# RPI_M_LED.net
KiCad netlist of a schematic drawn in EAGLE
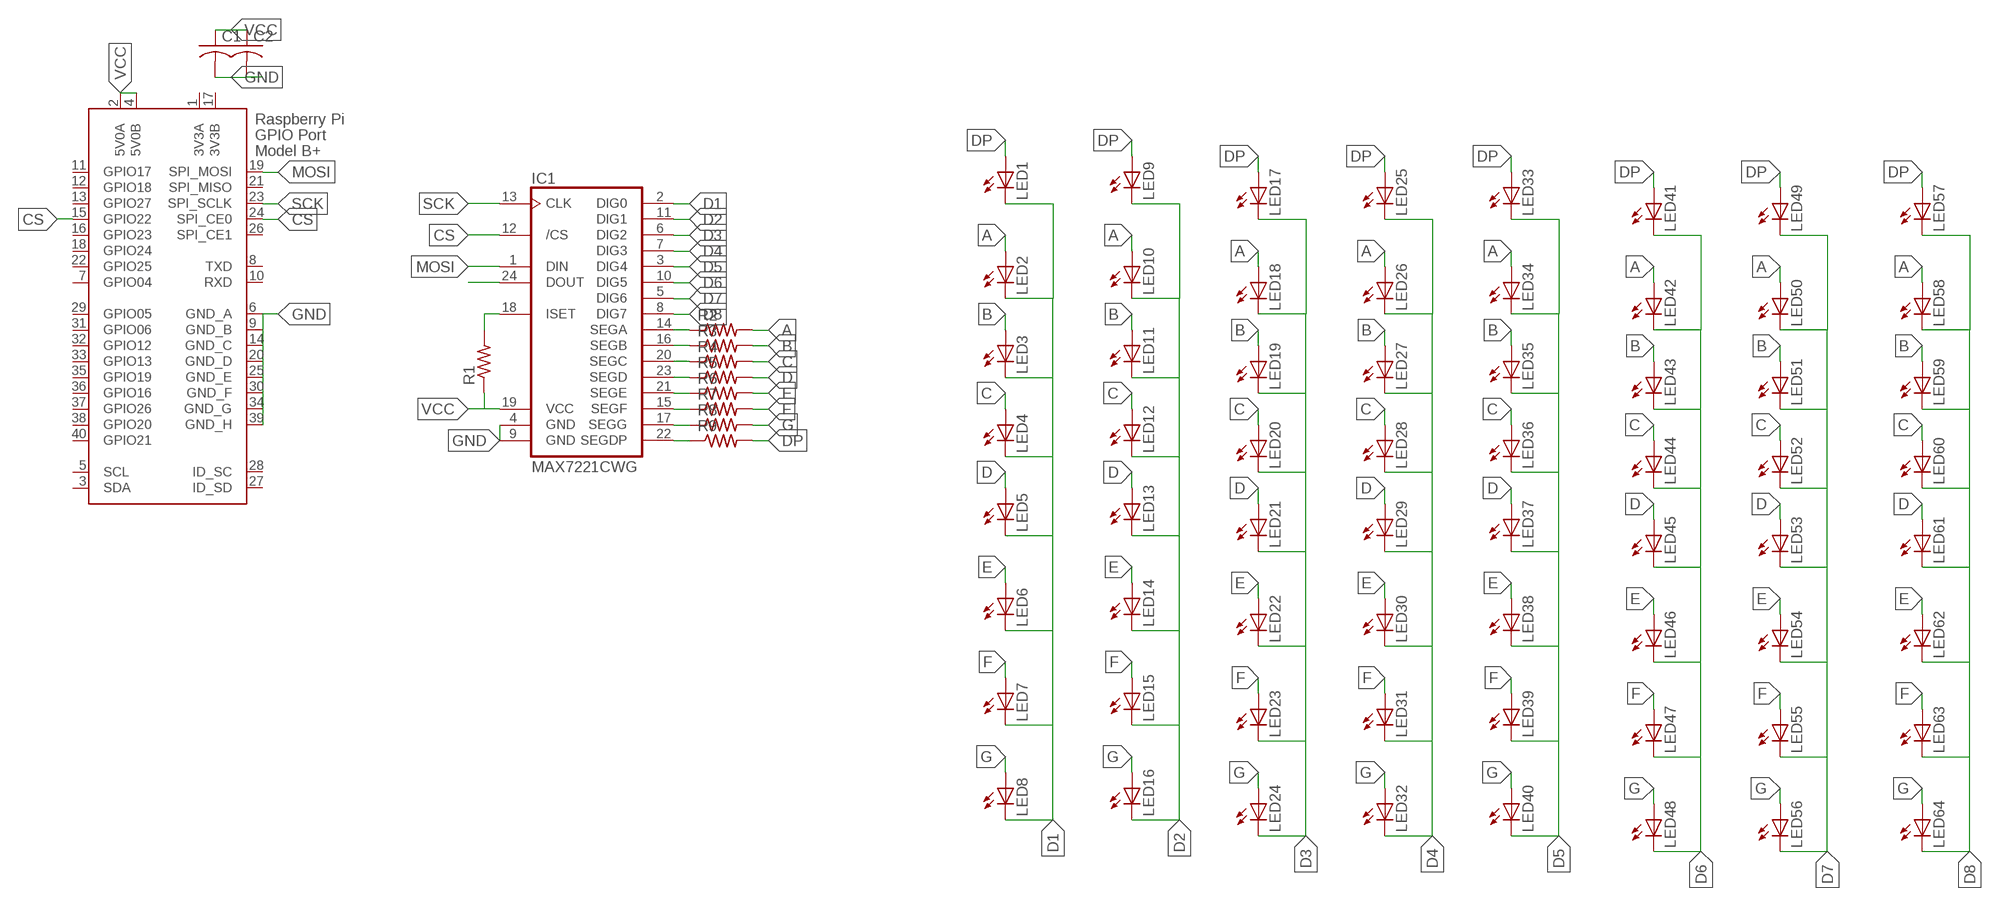
[diagram p0: schematic, sheet 1]

(export (version "E")
  (design (tool "Eeschema 10.0.6"))
  (components
    (comp (ref "C1")
      (value "C-USC0805")
      (footprint "eagle-import:C0805")
      (libsource (lib "eagle-import") (part "C-USC0805"))
    )
    (comp (ref "C2")
      (value "C-USC0805")
      (footprint "eagle-import:C0805")
      (libsource (lib "eagle-import") (part "C-USC0805"))
    )
    (comp (ref "IC1")
      (value "MAX7221CWG")
      (footprint "eagle-import:SO24W")
      (libsource (lib "eagle-import") (part "MAX7221WGC"))
    )
    (comp (ref "LED1")
      (value "LEDCHIPLED_0603")
      (footprint "eagle-import:CHIPLED_0603")
      (libsource (lib "eagle-import") (part "LEDCHIPLED_0603"))
    )
    (comp (ref "LED2")
      (value "LEDCHIPLED_0603")
      (footprint "eagle-import:CHIPLED_0603")
      (libsource (lib "eagle-import") (part "LEDCHIPLED_0603"))
    )
    (comp (ref "LED3")
      (value "LEDCHIPLED_0603")
      (footprint "eagle-import:CHIPLED_0603")
      (libsource (lib "eagle-import") (part "LEDCHIPLED_0603"))
    )
    (comp (ref "LED4")
      (value "LEDCHIPLED_0603")
      (footprint "eagle-import:CHIPLED_0603")
      (libsource (lib "eagle-import") (part "LEDCHIPLED_0603"))
    )
    (comp (ref "LED5")
      (value "LEDCHIPLED_0603")
      (footprint "eagle-import:CHIPLED_0603")
      (libsource (lib "eagle-import") (part "LEDCHIPLED_0603"))
    )
    (comp (ref "LED6")
      (value "LEDCHIPLED_0603")
      (footprint "eagle-import:CHIPLED_0603")
      (libsource (lib "eagle-import") (part "LEDCHIPLED_0603"))
    )
    (comp (ref "LED7")
      (value "LEDCHIPLED_0603")
      (footprint "eagle-import:CHIPLED_0603")
      (libsource (lib "eagle-import") (part "LEDCHIPLED_0603"))
    )
    (comp (ref "LED8")
      (value "LEDCHIPLED_0603")
      (footprint "eagle-import:CHIPLED_0603")
      (libsource (lib "eagle-import") (part "LEDCHIPLED_0603"))
    )
    (comp (ref "LED9")
      (value "LEDCHIPLED_0603")
      (footprint "eagle-import:CHIPLED_0603")
      (libsource (lib "eagle-import") (part "LEDCHIPLED_0603"))
    )
    (comp (ref "LED10")
      (value "LEDCHIPLED_0603")
      (footprint "eagle-import:CHIPLED_0603")
      (libsource (lib "eagle-import") (part "LEDCHIPLED_0603"))
    )
    (comp (ref "LED11")
      (value "LEDCHIPLED_0603")
      (footprint "eagle-import:CHIPLED_0603")
      (libsource (lib "eagle-import") (part "LEDCHIPLED_0603"))
    )
    (comp (ref "LED12")
      (value "LEDCHIPLED_0603")
      (footprint "eagle-import:CHIPLED_0603")
      (libsource (lib "eagle-import") (part "LEDCHIPLED_0603"))
    )
    (comp (ref "LED13")
      (value "LEDCHIPLED_0603")
      (footprint "eagle-import:CHIPLED_0603")
      (libsource (lib "eagle-import") (part "LEDCHIPLED_0603"))
    )
    (comp (ref "LED14")
      (value "LEDCHIPLED_0603")
      (footprint "eagle-import:CHIPLED_0603")
      (libsource (lib "eagle-import") (part "LEDCHIPLED_0603"))
    )
    (comp (ref "LED15")
      (value "LEDCHIPLED_0603")
      (footprint "eagle-import:CHIPLED_0603")
      (libsource (lib "eagle-import") (part "LEDCHIPLED_0603"))
    )
    (comp (ref "LED16")
      (value "LEDCHIPLED_0603")
      (footprint "eagle-import:CHIPLED_0603")
      (libsource (lib "eagle-import") (part "LEDCHIPLED_0603"))
    )
    (comp (ref "LED17")
      (value "LEDCHIPLED_0603")
      (footprint "eagle-import:CHIPLED_0603")
      (libsource (lib "eagle-import") (part "LEDCHIPLED_0603"))
    )
    (comp (ref "LED18")
      (value "LEDCHIPLED_0603")
      (footprint "eagle-import:CHIPLED_0603")
      (libsource (lib "eagle-import") (part "LEDCHIPLED_0603"))
    )
    (comp (ref "LED19")
      (value "LEDCHIPLED_0603")
      (footprint "eagle-import:CHIPLED_0603")
      (libsource (lib "eagle-import") (part "LEDCHIPLED_0603"))
    )
    (comp (ref "LED20")
      (value "LEDCHIPLED_0603")
      (footprint "eagle-import:CHIPLED_0603")
      (libsource (lib "eagle-import") (part "LEDCHIPLED_0603"))
    )
    (comp (ref "LED21")
      (value "LEDCHIPLED_0603")
      (footprint "eagle-import:CHIPLED_0603")
      (libsource (lib "eagle-import") (part "LEDCHIPLED_0603"))
    )
    (comp (ref "LED22")
      (value "LEDCHIPLED_0603")
      (footprint "eagle-import:CHIPLED_0603")
      (libsource (lib "eagle-import") (part "LEDCHIPLED_0603"))
    )
    (comp (ref "LED23")
      (value "LEDCHIPLED_0603")
      (footprint "eagle-import:CHIPLED_0603")
      (libsource (lib "eagle-import") (part "LEDCHIPLED_0603"))
    )
    (comp (ref "LED24")
      (value "LEDCHIPLED_0603")
      (footprint "eagle-import:CHIPLED_0603")
      (libsource (lib "eagle-import") (part "LEDCHIPLED_0603"))
    )
    (comp (ref "LED25")
      (value "LEDCHIPLED_0603")
      (footprint "eagle-import:CHIPLED_0603")
      (libsource (lib "eagle-import") (part "LEDCHIPLED_0603"))
    )
    (comp (ref "LED26")
      (value "LEDCHIPLED_0603")
      (footprint "eagle-import:CHIPLED_0603")
      (libsource (lib "eagle-import") (part "LEDCHIPLED_0603"))
    )
    (comp (ref "LED27")
      (value "LEDCHIPLED_0603")
      (footprint "eagle-import:CHIPLED_0603")
      (libsource (lib "eagle-import") (part "LEDCHIPLED_0603"))
    )
    (comp (ref "LED28")
      (value "LEDCHIPLED_0603")
      (footprint "eagle-import:CHIPLED_0603")
      (libsource (lib "eagle-import") (part "LEDCHIPLED_0603"))
    )
    (comp (ref "LED29")
      (value "LEDCHIPLED_0603")
      (footprint "eagle-import:CHIPLED_0603")
      (libsource (lib "eagle-import") (part "LEDCHIPLED_0603"))
    )
    (comp (ref "LED30")
      (value "LEDCHIPLED_0603")
      (footprint "eagle-import:CHIPLED_0603")
      (libsource (lib "eagle-import") (part "LEDCHIPLED_0603"))
    )
    (comp (ref "LED31")
      (value "LEDCHIPLED_0603")
      (footprint "eagle-import:CHIPLED_0603")
      (libsource (lib "eagle-import") (part "LEDCHIPLED_0603"))
    )
    (comp (ref "LED32")
      (value "LEDCHIPLED_0603")
      (footprint "eagle-import:CHIPLED_0603")
      (libsource (lib "eagle-import") (part "LEDCHIPLED_0603"))
    )
    (comp (ref "LED33")
      (value "LEDCHIPLED_0603")
      (footprint "eagle-import:CHIPLED_0603")
      (libsource (lib "eagle-import") (part "LEDCHIPLED_0603"))
    )
    (comp (ref "LED34")
      (value "LEDCHIPLED_0603")
      (footprint "eagle-import:CHIPLED_0603")
      (libsource (lib "eagle-import") (part "LEDCHIPLED_0603"))
    )
    (comp (ref "LED35")
      (value "LEDCHIPLED_0603")
      (footprint "eagle-import:CHIPLED_0603")
      (libsource (lib "eagle-import") (part "LEDCHIPLED_0603"))
    )
    (comp (ref "LED36")
      (value "LEDCHIPLED_0603")
      (footprint "eagle-import:CHIPLED_0603")
      (libsource (lib "eagle-import") (part "LEDCHIPLED_0603"))
    )
    (comp (ref "LED37")
      (value "LEDCHIPLED_0603")
      (footprint "eagle-import:CHIPLED_0603")
      (libsource (lib "eagle-import") (part "LEDCHIPLED_0603"))
    )
    (comp (ref "LED38")
      (value "LEDCHIPLED_0603")
      (footprint "eagle-import:CHIPLED_0603")
      (libsource (lib "eagle-import") (part "LEDCHIPLED_0603"))
    )
    (comp (ref "LED39")
      (value "LEDCHIPLED_0603")
      (footprint "eagle-import:CHIPLED_0603")
      (libsource (lib "eagle-import") (part "LEDCHIPLED_0603"))
    )
    (comp (ref "LED40")
      (value "LEDCHIPLED_0603")
      (footprint "eagle-import:CHIPLED_0603")
      (libsource (lib "eagle-import") (part "LEDCHIPLED_0603"))
    )
    (comp (ref "LED41")
      (value "LEDCHIPLED_0603")
      (footprint "eagle-import:CHIPLED_0603")
      (libsource (lib "eagle-import") (part "LEDCHIPLED_0603"))
    )
    (comp (ref "LED42")
      (value "LEDCHIPLED_0603")
      (footprint "eagle-import:CHIPLED_0603")
      (libsource (lib "eagle-import") (part "LEDCHIPLED_0603"))
    )
    (comp (ref "LED43")
      (value "LEDCHIPLED_0603")
      (footprint "eagle-import:CHIPLED_0603")
      (libsource (lib "eagle-import") (part "LEDCHIPLED_0603"))
    )
    (comp (ref "LED44")
      (value "LEDCHIPLED_0603")
      (footprint "eagle-import:CHIPLED_0603")
      (libsource (lib "eagle-import") (part "LEDCHIPLED_0603"))
    )
    (comp (ref "LED45")
      (value "LEDCHIPLED_0603")
      (footprint "eagle-import:CHIPLED_0603")
      (libsource (lib "eagle-import") (part "LEDCHIPLED_0603"))
    )
    (comp (ref "LED46")
      (value "LEDCHIPLED_0603")
      (footprint "eagle-import:CHIPLED_0603")
      (libsource (lib "eagle-import") (part "LEDCHIPLED_0603"))
    )
    (comp (ref "LED47")
      (value "LEDCHIPLED_0603")
      (footprint "eagle-import:CHIPLED_0603")
      (libsource (lib "eagle-import") (part "LEDCHIPLED_0603"))
    )
    (comp (ref "LED48")
      (value "LEDCHIPLED_0603")
      (footprint "eagle-import:CHIPLED_0603")
      (libsource (lib "eagle-import") (part "LEDCHIPLED_0603"))
    )
    (comp (ref "LED49")
      (value "LEDCHIPLED_0603")
      (footprint "eagle-import:CHIPLED_0603")
      (libsource (lib "eagle-import") (part "LEDCHIPLED_0603"))
    )
    (comp (ref "LED50")
      (value "LEDCHIPLED_0603")
      (footprint "eagle-import:CHIPLED_0603")
      (libsource (lib "eagle-import") (part "LEDCHIPLED_0603"))
    )
    (comp (ref "LED51")
      (value "LEDCHIPLED_0603")
      (footprint "eagle-import:CHIPLED_0603")
      (libsource (lib "eagle-import") (part "LEDCHIPLED_0603"))
    )
    (comp (ref "LED52")
      (value "LEDCHIPLED_0603")
      (footprint "eagle-import:CHIPLED_0603")
      (libsource (lib "eagle-import") (part "LEDCHIPLED_0603"))
    )
    (comp (ref "LED53")
      (value "LEDCHIPLED_0603")
      (footprint "eagle-import:CHIPLED_0603")
      (libsource (lib "eagle-import") (part "LEDCHIPLED_0603"))
    )
    (comp (ref "LED54")
      (value "LEDCHIPLED_0603")
      (footprint "eagle-import:CHIPLED_0603")
      (libsource (lib "eagle-import") (part "LEDCHIPLED_0603"))
    )
    (comp (ref "LED55")
      (value "LEDCHIPLED_0603")
      (footprint "eagle-import:CHIPLED_0603")
      (libsource (lib "eagle-import") (part "LEDCHIPLED_0603"))
    )
    (comp (ref "LED56")
      (value "LEDCHIPLED_0603")
      (footprint "eagle-import:CHIPLED_0603")
      (libsource (lib "eagle-import") (part "LEDCHIPLED_0603"))
    )
    (comp (ref "LED57")
      (value "LEDCHIPLED_0603")
      (footprint "eagle-import:CHIPLED_0603")
      (libsource (lib "eagle-import") (part "LEDCHIPLED_0603"))
    )
    (comp (ref "LED58")
      (value "LEDCHIPLED_0603")
      (footprint "eagle-import:CHIPLED_0603")
      (libsource (lib "eagle-import") (part "LEDCHIPLED_0603"))
    )
    (comp (ref "LED59")
      (value "LEDCHIPLED_0603")
      (footprint "eagle-import:CHIPLED_0603")
      (libsource (lib "eagle-import") (part "LEDCHIPLED_0603"))
    )
    (comp (ref "LED60")
      (value "LEDCHIPLED_0603")
      (footprint "eagle-import:CHIPLED_0603")
      (libsource (lib "eagle-import") (part "LEDCHIPLED_0603"))
    )
    (comp (ref "LED61")
      (value "LEDCHIPLED_0603")
      (footprint "eagle-import:CHIPLED_0603")
      (libsource (lib "eagle-import") (part "LEDCHIPLED_0603"))
    )
    (comp (ref "LED62")
      (value "LEDCHIPLED_0603")
      (footprint "eagle-import:CHIPLED_0603")
      (libsource (lib "eagle-import") (part "LEDCHIPLED_0603"))
    )
    (comp (ref "LED63")
      (value "LEDCHIPLED_0603")
      (footprint "eagle-import:CHIPLED_0603")
      (libsource (lib "eagle-import") (part "LEDCHIPLED_0603"))
    )
    (comp (ref "LED64")
      (value "LEDCHIPLED_0603")
      (footprint "eagle-import:CHIPLED_0603")
      (libsource (lib "eagle-import") (part "LEDCHIPLED_0603"))
    )
    (comp (ref "R1")
      (value "R-US_R0805")
      (footprint "eagle-import:R0805")
      (libsource (lib "eagle-import") (part "R-US_R0805"))
    )
    (comp (ref "R2")
      (value "R-US_R0603")
      (footprint "eagle-import:R0603")
      (libsource (lib "eagle-import") (part "R-US_R0603"))
    )
    (comp (ref "R3")
      (value "R-US_R0603")
      (footprint "eagle-import:R0603")
      (libsource (lib "eagle-import") (part "R-US_R0603"))
    )
    (comp (ref "R4")
      (value "R-US_R0603")
      (footprint "eagle-import:R0603")
      (libsource (lib "eagle-import") (part "R-US_R0603"))
    )
    (comp (ref "R5")
      (value "R-US_R0603")
      (footprint "eagle-import:R0603")
      (libsource (lib "eagle-import") (part "R-US_R0603"))
    )
    (comp (ref "R6")
      (value "R-US_R0603")
      (footprint "eagle-import:R0603")
      (libsource (lib "eagle-import") (part "R-US_R0603"))
    )
    (comp (ref "R7")
      (value "R-US_R0603")
      (footprint "eagle-import:R0603")
      (libsource (lib "eagle-import") (part "R-US_R0603"))
    )
    (comp (ref "R8")
      (value "R-US_R0603")
      (footprint "eagle-import:R0603")
      (libsource (lib "eagle-import") (part "R-US_R0603"))
    )
    (comp (ref "R9")
      (value "R-US_R0603")
      (footprint "eagle-import:R0603")
      (libsource (lib "eagle-import") (part "R-US_R0603"))
    )
    (comp (ref "X1")
      (value "RASPI_GPIO_B+#_PIN")
      (footprint "eagle-import:RASPI_GPIO_B+_PIN")
      (libsource (lib "eagle-import") (part "RASPI_GPIO_B+#_PIN"))
    )
  )
  (nets
    (net (code "1") (name "/3V3A") (class "Default")
      (node (ref "X1") (pin "1") (pinfunction "3V3A_1") (pintype "power_in"))
    )
    (net (code "2") (name "/3V3B") (class "Default")
      (node (ref "X1") (pin "17") (pinfunction "3V3B_17") (pintype "power_in"))
    )
    (net (code "3") (name "A") (class "Default")
      (node (ref "LED10") (pin "A") (pinfunction "A_A") (pintype "passive"))
      (node (ref "LED18") (pin "A") (pinfunction "A_A") (pintype "passive"))
      (node (ref "LED2") (pin "A") (pinfunction "A_A") (pintype "passive"))
      (node (ref "LED26") (pin "A") (pinfunction "A_A") (pintype "passive"))
      (node (ref "LED34") (pin "A") (pinfunction "A_A") (pintype "passive"))
      (node (ref "LED42") (pin "A") (pinfunction "A_A") (pintype "passive"))
      (node (ref "LED50") (pin "A") (pinfunction "A_A") (pintype "passive"))
      (node (ref "LED58") (pin "A") (pinfunction "A_A") (pintype "passive"))
      (node (ref "R2") (pin "2") (pinfunction "2_2") (pintype "passive"))
    )
    (net (code "4") (name "B") (class "Default")
      (node (ref "LED11") (pin "A") (pinfunction "A_A") (pintype "passive"))
      (node (ref "LED19") (pin "A") (pinfunction "A_A") (pintype "passive"))
      (node (ref "LED27") (pin "A") (pinfunction "A_A") (pintype "passive"))
      (node (ref "LED3") (pin "A") (pinfunction "A_A") (pintype "passive"))
      (node (ref "LED35") (pin "A") (pinfunction "A_A") (pintype "passive"))
      (node (ref "LED43") (pin "A") (pinfunction "A_A") (pintype "passive"))
      (node (ref "LED51") (pin "A") (pinfunction "A_A") (pintype "passive"))
      (node (ref "LED59") (pin "A") (pinfunction "A_A") (pintype "passive"))
      (node (ref "R3") (pin "2") (pinfunction "2_2") (pintype "passive"))
    )
    (net (code "5") (name "C") (class "Default")
      (node (ref "LED12") (pin "A") (pinfunction "A_A") (pintype "passive"))
      (node (ref "LED20") (pin "A") (pinfunction "A_A") (pintype "passive"))
      (node (ref "LED28") (pin "A") (pinfunction "A_A") (pintype "passive"))
      (node (ref "LED36") (pin "A") (pinfunction "A_A") (pintype "passive"))
      (node (ref "LED4") (pin "A") (pinfunction "A_A") (pintype "passive"))
      (node (ref "LED44") (pin "A") (pinfunction "A_A") (pintype "passive"))
      (node (ref "LED52") (pin "A") (pinfunction "A_A") (pintype "passive"))
      (node (ref "LED60") (pin "A") (pinfunction "A_A") (pintype "passive"))
      (node (ref "R4") (pin "2") (pinfunction "2_2") (pintype "passive"))
    )
    (net (code "6") (name "CS") (class "Default")
      (node (ref "IC1") (pin "12") (pinfunction "/CS_12") (pintype "input"))
      (node (ref "X1") (pin "15") (pinfunction "GPIO22_15") (pintype "bidirectional"))
      (node (ref "X1") (pin "24") (pinfunction "SPI_CE0_24") (pintype "bidirectional"))
    )
    (net (code "7") (name "D") (class "Default")
      (node (ref "LED13") (pin "A") (pinfunction "A_A") (pintype "passive"))
      (node (ref "LED21") (pin "A") (pinfunction "A_A") (pintype "passive"))
      (node (ref "LED29") (pin "A") (pinfunction "A_A") (pintype "passive"))
      (node (ref "LED37") (pin "A") (pinfunction "A_A") (pintype "passive"))
      (node (ref "LED45") (pin "A") (pinfunction "A_A") (pintype "passive"))
      (node (ref "LED5") (pin "A") (pinfunction "A_A") (pintype "passive"))
      (node (ref "LED53") (pin "A") (pinfunction "A_A") (pintype "passive"))
      (node (ref "LED61") (pin "A") (pinfunction "A_A") (pintype "passive"))
      (node (ref "R5") (pin "2") (pinfunction "2_2") (pintype "passive"))
    )
    (net (code "8") (name "D1") (class "Default")
      (node (ref "IC1") (pin "2") (pinfunction "DIG0_2") (pintype "open_collector"))
      (node (ref "LED1") (pin "C") (pinfunction "C_C") (pintype "passive"))
      (node (ref "LED2") (pin "C") (pinfunction "C_C") (pintype "passive"))
      (node (ref "LED3") (pin "C") (pinfunction "C_C") (pintype "passive"))
      (node (ref "LED4") (pin "C") (pinfunction "C_C") (pintype "passive"))
      (node (ref "LED5") (pin "C") (pinfunction "C_C") (pintype "passive"))
      (node (ref "LED6") (pin "C") (pinfunction "C_C") (pintype "passive"))
      (node (ref "LED7") (pin "C") (pinfunction "C_C") (pintype "passive"))
      (node (ref "LED8") (pin "C") (pinfunction "C_C") (pintype "passive"))
    )
    (net (code "9") (name "D2") (class "Default")
      (node (ref "IC1") (pin "11") (pinfunction "DIG1_11") (pintype "open_collector"))
      (node (ref "LED10") (pin "C") (pinfunction "C_C") (pintype "passive"))
      (node (ref "LED11") (pin "C") (pinfunction "C_C") (pintype "passive"))
      (node (ref "LED12") (pin "C") (pinfunction "C_C") (pintype "passive"))
      (node (ref "LED13") (pin "C") (pinfunction "C_C") (pintype "passive"))
      (node (ref "LED14") (pin "C") (pinfunction "C_C") (pintype "passive"))
      (node (ref "LED15") (pin "C") (pinfunction "C_C") (pintype "passive"))
      (node (ref "LED16") (pin "C") (pinfunction "C_C") (pintype "passive"))
      (node (ref "LED9") (pin "C") (pinfunction "C_C") (pintype "passive"))
    )
    (net (code "10") (name "D3") (class "Default")
      (node (ref "IC1") (pin "6") (pinfunction "DIG2_6") (pintype "open_collector"))
      (node (ref "LED17") (pin "C") (pinfunction "C_C") (pintype "passive"))
      (node (ref "LED18") (pin "C") (pinfunction "C_C") (pintype "passive"))
      (node (ref "LED19") (pin "C") (pinfunction "C_C") (pintype "passive"))
      (node (ref "LED20") (pin "C") (pinfunction "C_C") (pintype "passive"))
      (node (ref "LED21") (pin "C") (pinfunction "C_C") (pintype "passive"))
      (node (ref "LED22") (pin "C") (pinfunction "C_C") (pintype "passive"))
      (node (ref "LED23") (pin "C") (pinfunction "C_C") (pintype "passive"))
      (node (ref "LED24") (pin "C") (pinfunction "C_C") (pintype "passive"))
    )
    (net (code "11") (name "D4") (class "Default")
      (node (ref "IC1") (pin "7") (pinfunction "DIG3_7") (pintype "open_collector"))
      (node (ref "LED25") (pin "C") (pinfunction "C_C") (pintype "passive"))
      (node (ref "LED26") (pin "C") (pinfunction "C_C") (pintype "passive"))
      (node (ref "LED27") (pin "C") (pinfunction "C_C") (pintype "passive"))
      (node (ref "LED28") (pin "C") (pinfunction "C_C") (pintype "passive"))
      (node (ref "LED29") (pin "C") (pinfunction "C_C") (pintype "passive"))
      (node (ref "LED30") (pin "C") (pinfunction "C_C") (pintype "passive"))
      (node (ref "LED31") (pin "C") (pinfunction "C_C") (pintype "passive"))
      (node (ref "LED32") (pin "C") (pinfunction "C_C") (pintype "passive"))
    )
    (net (code "12") (name "D5") (class "Default")
      (node (ref "IC1") (pin "3") (pinfunction "DIG4_3") (pintype "open_collector"))
      (node (ref "LED33") (pin "C") (pinfunction "C_C") (pintype "passive"))
      (node (ref "LED34") (pin "C") (pinfunction "C_C") (pintype "passive"))
      (node (ref "LED35") (pin "C") (pinfunction "C_C") (pintype "passive"))
      (node (ref "LED36") (pin "C") (pinfunction "C_C") (pintype "passive"))
      (node (ref "LED37") (pin "C") (pinfunction "C_C") (pintype "passive"))
      (node (ref "LED38") (pin "C") (pinfunction "C_C") (pintype "passive"))
      (node (ref "LED39") (pin "C") (pinfunction "C_C") (pintype "passive"))
      (node (ref "LED40") (pin "C") (pinfunction "C_C") (pintype "passive"))
    )
    (net (code "13") (name "D6") (class "Default")
      (node (ref "IC1") (pin "10") (pinfunction "DIG5_10") (pintype "open_collector"))
      (node (ref "LED41") (pin "C") (pinfunction "C_C") (pintype "passive"))
      (node (ref "LED42") (pin "C") (pinfunction "C_C") (pintype "passive"))
      (node (ref "LED43") (pin "C") (pinfunction "C_C") (pintype "passive"))
      (node (ref "LED44") (pin "C") (pinfunction "C_C") (pintype "passive"))
      (node (ref "LED45") (pin "C") (pinfunction "C_C") (pintype "passive"))
      (node (ref "LED46") (pin "C") (pinfunction "C_C") (pintype "passive"))
      (node (ref "LED47") (pin "C") (pinfunction "C_C") (pintype "passive"))
      (node (ref "LED48") (pin "C") (pinfunction "C_C") (pintype "passive"))
    )
    (net (code "14") (name "D7") (class "Default")
      (node (ref "IC1") (pin "5") (pinfunction "DIG6_5") (pintype "open_collector"))
      (node (ref "LED49") (pin "C") (pinfunction "C_C") (pintype "passive"))
      (node (ref "LED50") (pin "C") (pinfunction "C_C") (pintype "passive"))
      (node (ref "LED51") (pin "C") (pinfunction "C_C") (pintype "passive"))
      (node (ref "LED52") (pin "C") (pinfunction "C_C") (pintype "passive"))
      (node (ref "LED53") (pin "C") (pinfunction "C_C") (pintype "passive"))
      (node (ref "LED54") (pin "C") (pinfunction "C_C") (pintype "passive"))
      (node (ref "LED55") (pin "C") (pinfunction "C_C") (pintype "passive"))
      (node (ref "LED56") (pin "C") (pinfunction "C_C") (pintype "passive"))
    )
    (net (code "15") (name "D8") (class "Default")
      (node (ref "IC1") (pin "8") (pinfunction "DIG7_8") (pintype "open_collector"))
      (node (ref "LED57") (pin "C") (pinfunction "C_C") (pintype "passive"))
      (node (ref "LED58") (pin "C") (pinfunction "C_C") (pintype "passive"))
      (node (ref "LED59") (pin "C") (pinfunction "C_C") (pintype "passive"))
      (node (ref "LED60") (pin "C") (pinfunction "C_C") (pintype "passive"))
      (node (ref "LED61") (pin "C") (pinfunction "C_C") (pintype "passive"))
      (node (ref "LED62") (pin "C") (pinfunction "C_C") (pintype "passive"))
      (node (ref "LED63") (pin "C") (pinfunction "C_C") (pintype "passive"))
      (node (ref "LED64") (pin "C") (pinfunction "C_C") (pintype "passive"))
    )
    (net (code "16") (name "DP") (class "Default")
      (node (ref "LED1") (pin "A") (pinfunction "A_A") (pintype "passive"))
      (node (ref "LED17") (pin "A") (pinfunction "A_A") (pintype "passive"))
      (node (ref "LED25") (pin "A") (pinfunction "A_A") (pintype "passive"))
      (node (ref "LED33") (pin "A") (pinfunction "A_A") (pintype "passive"))
      (node (ref "LED41") (pin "A") (pinfunction "A_A") (pintype "passive"))
      (node (ref "LED49") (pin "A") (pinfunction "A_A") (pintype "passive"))
      (node (ref "LED57") (pin "A") (pinfunction "A_A") (pintype "passive"))
      (node (ref "LED9") (pin "A") (pinfunction "A_A") (pintype "passive"))
      (node (ref "R9") (pin "2") (pinfunction "2_2") (pintype "passive"))
    )
    (net (code "17") (name "E") (class "Default")
      (node (ref "LED14") (pin "A") (pinfunction "A_A") (pintype "passive"))
      (node (ref "LED22") (pin "A") (pinfunction "A_A") (pintype "passive"))
      (node (ref "LED30") (pin "A") (pinfunction "A_A") (pintype "passive"))
      (node (ref "LED38") (pin "A") (pinfunction "A_A") (pintype "passive"))
      (node (ref "LED46") (pin "A") (pinfunction "A_A") (pintype "passive"))
      (node (ref "LED54") (pin "A") (pinfunction "A_A") (pintype "passive"))
      (node (ref "LED6") (pin "A") (pinfunction "A_A") (pintype "passive"))
      (node (ref "LED62") (pin "A") (pinfunction "A_A") (pintype "passive"))
      (node (ref "R6") (pin "2") (pinfunction "2_2") (pintype "passive"))
    )
    (net (code "18") (name "F") (class "Default")
      (node (ref "LED15") (pin "A") (pinfunction "A_A") (pintype "passive"))
      (node (ref "LED23") (pin "A") (pinfunction "A_A") (pintype "passive"))
      (node (ref "LED31") (pin "A") (pinfunction "A_A") (pintype "passive"))
      (node (ref "LED39") (pin "A") (pinfunction "A_A") (pintype "passive"))
      (node (ref "LED47") (pin "A") (pinfunction "A_A") (pintype "passive"))
      (node (ref "LED55") (pin "A") (pinfunction "A_A") (pintype "passive"))
      (node (ref "LED63") (pin "A") (pinfunction "A_A") (pintype "passive"))
      (node (ref "LED7") (pin "A") (pinfunction "A_A") (pintype "passive"))
      (node (ref "R7") (pin "2") (pinfunction "2_2") (pintype "passive"))
    )
    (net (code "19") (name "G") (class "Default")
      (node (ref "LED16") (pin "A") (pinfunction "A_A") (pintype "passive"))
      (node (ref "LED24") (pin "A") (pinfunction "A_A") (pintype "passive"))
      (node (ref "LED32") (pin "A") (pinfunction "A_A") (pintype "passive"))
      (node (ref "LED40") (pin "A") (pinfunction "A_A") (pintype "passive"))
      (node (ref "LED48") (pin "A") (pinfunction "A_A") (pintype "passive"))
      (node (ref "LED56") (pin "A") (pinfunction "A_A") (pintype "passive"))
      (node (ref "LED64") (pin "A") (pinfunction "A_A") (pintype "passive"))
      (node (ref "LED8") (pin "A") (pinfunction "A_A") (pintype "passive"))
      (node (ref "R8") (pin "2") (pinfunction "2_2") (pintype "passive"))
    )
    (net (code "20") (name "GND") (class "Default")
      (node (ref "C1") (pin "2") (pinfunction "2_2") (pintype "passive"))
      (node (ref "C2") (pin "2") (pinfunction "2_2") (pintype "passive"))
      (node (ref "IC1") (pin "4") (pinfunction "GND_4") (pintype "power_in"))
      (node (ref "IC1") (pin "9") (pinfunction "GND_9") (pintype "power_in"))
      (node (ref "X1") (pin "14") (pinfunction "GND_C_14") (pintype "power_in"))
      (node (ref "X1") (pin "20") (pinfunction "GND_D_20") (pintype "power_in"))
      (node (ref "X1") (pin "25") (pinfunction "GND_E_25") (pintype "power_in"))
      (node (ref "X1") (pin "30") (pinfunction "GND_F_30") (pintype "power_in"))
      (node (ref "X1") (pin "34") (pinfunction "GND_G_34") (pintype "power_in"))
      (node (ref "X1") (pin "39") (pinfunction "GND_H_39") (pintype "power_in"))
      (node (ref "X1") (pin "6") (pinfunction "GND_A_6") (pintype "power_in"))
      (node (ref "X1") (pin "9") (pinfunction "GND_B_9") (pintype "power_in"))
    )
    (net (code "21") (name "MOSI") (class "Default")
      (node (ref "IC1") (pin "1") (pinfunction "DIN_1") (pintype "input"))
      (node (ref "X1") (pin "19") (pinfunction "SPI_MOSI_19") (pintype "bidirectional"))
    )
    (net (code "22") (name "Net-(IC1-ISET)") (class "Default")
      (node (ref "IC1") (pin "18") (pinfunction "ISET_18") (pintype "input"))
      (node (ref "R1") (pin "2") (pinfunction "2_2") (pintype "passive"))
    )
    (net (code "23") (name "Net-(IC1-SEGA)") (class "Default")
      (node (ref "IC1") (pin "14") (pinfunction "SEGA_14") (pintype "output"))
      (node (ref "R2") (pin "1") (pinfunction "1_1") (pintype "passive"))
    )
    (net (code "24") (name "Net-(IC1-SEGB)") (class "Default")
      (node (ref "IC1") (pin "16") (pinfunction "SEGB_16") (pintype "output"))
      (node (ref "R3") (pin "1") (pinfunction "1_1") (pintype "passive"))
    )
    (net (code "25") (name "Net-(IC1-SEGC)") (class "Default")
      (node (ref "IC1") (pin "20") (pinfunction "SEGC_20") (pintype "output"))
      (node (ref "R4") (pin "1") (pinfunction "1_1") (pintype "passive"))
    )
    (net (code "26") (name "Net-(IC1-SEGD)") (class "Default")
      (node (ref "IC1") (pin "23") (pinfunction "SEGD_23") (pintype "output"))
      (node (ref "R5") (pin "1") (pinfunction "1_1") (pintype "passive"))
    )
    (net (code "27") (name "Net-(IC1-SEGDP)") (class "Default")
      (node (ref "IC1") (pin "22") (pinfunction "SEGDP_22") (pintype "output"))
      (node (ref "R9") (pin "1") (pinfunction "1_1") (pintype "passive"))
    )
    (net (code "28") (name "Net-(IC1-SEGE)") (class "Default")
      (node (ref "IC1") (pin "21") (pinfunction "SEGE_21") (pintype "output"))
      (node (ref "R6") (pin "1") (pinfunction "1_1") (pintype "passive"))
    )
    (net (code "29") (name "Net-(IC1-SEGF)") (class "Default")
      (node (ref "IC1") (pin "15") (pinfunction "SEGF_15") (pintype "output"))
      (node (ref "R7") (pin "1") (pinfunction "1_1") (pintype "passive"))
    )
    (net (code "30") (name "Net-(IC1-SEGG)") (class "Default")
      (node (ref "IC1") (pin "17") (pinfunction "SEGG_17") (pintype "output"))
      (node (ref "R8") (pin "1") (pinfunction "1_1") (pintype "passive"))
    )
    (net (code "31") (name "SCK") (class "Default")
      (node (ref "IC1") (pin "13") (pinfunction "CLK_13") (pintype "input"))
      (node (ref "X1") (pin "23") (pinfunction "SPI_SCLK_23") (pintype "bidirectional"))
    )
    (net (code "32") (name "VCC") (class "Default")
      (node (ref "C1") (pin "1") (pinfunction "1_1") (pintype "passive"))
      (node (ref "C2") (pin "1") (pinfunction "1_1") (pintype "passive"))
      (node (ref "IC1") (pin "19") (pinfunction "VCC_19") (pintype "power_in"))
      (node (ref "R1") (pin "1") (pinfunction "1_1") (pintype "passive"))
      (node (ref "X1") (pin "2") (pinfunction "5V0A_2") (pintype "power_in"))
      (node (ref "X1") (pin "4") (pinfunction "5V0B_4") (pintype "power_in"))
    )
    (net (code "33") (name "unconnected-(IC1-DOUT-Pad24)") (class "Default")
      (node (ref "IC1") (pin "24") (pinfunction "DOUT_24") (pintype "output"))
    )
    (net (code "34") (name "unconnected-(X1-GPIO04-Pad7)") (class "Default")
      (node (ref "X1") (pin "7") (pinfunction "GPIO04_7") (pintype "bidirectional"))
    )
    (net (code "35") (name "unconnected-(X1-GPIO05-Pad29)") (class "Default")
      (node (ref "X1") (pin "29") (pinfunction "GPIO05_29") (pintype "no_connect"))
    )
    (net (code "36") (name "unconnected-(X1-GPIO06-Pad31)") (class "Default")
      (node (ref "X1") (pin "31") (pinfunction "GPIO06_31") (pintype "no_connect"))
    )
    (net (code "37") (name "unconnected-(X1-GPIO12-Pad32)") (class "Default")
      (node (ref "X1") (pin "32") (pinfunction "GPIO12_32") (pintype "no_connect"))
    )
    (net (code "38") (name "unconnected-(X1-GPIO13-Pad33)") (class "Default")
      (node (ref "X1") (pin "33") (pinfunction "GPIO13_33") (pintype "no_connect"))
    )
    (net (code "39") (name "unconnected-(X1-GPIO16-Pad36)") (class "Default")
      (node (ref "X1") (pin "36") (pinfunction "GPIO16_36") (pintype "no_connect"))
    )
    (net (code "40") (name "unconnected-(X1-GPIO17-Pad11)") (class "Default")
      (node (ref "X1") (pin "11") (pinfunction "GPIO17_11") (pintype "bidirectional"))
    )
    (net (code "41") (name "unconnected-(X1-GPIO18-Pad12)") (class "Default")
      (node (ref "X1") (pin "12") (pinfunction "GPIO18_12") (pintype "bidirectional"))
    )
    (net (code "42") (name "unconnected-(X1-GPIO19-Pad35)") (class "Default")
      (node (ref "X1") (pin "35") (pinfunction "GPIO19_35") (pintype "no_connect"))
    )
    (net (code "43") (name "unconnected-(X1-GPIO20-Pad38)") (class "Default")
      (node (ref "X1") (pin "38") (pinfunction "GPIO20_38") (pintype "no_connect"))
    )
    (net (code "44") (name "unconnected-(X1-GPIO21-Pad40)") (class "Default")
      (node (ref "X1") (pin "40") (pinfunction "GPIO21_40") (pintype "no_connect"))
    )
    (net (code "45") (name "unconnected-(X1-GPIO23-Pad16)") (class "Default")
      (node (ref "X1") (pin "16") (pinfunction "GPIO23_16") (pintype "bidirectional"))
    )
    (net (code "46") (name "unconnected-(X1-GPIO24-Pad18)") (class "Default")
      (node (ref "X1") (pin "18") (pinfunction "GPIO24_18") (pintype "bidirectional"))
    )
    (net (code "47") (name "unconnected-(X1-GPIO25-Pad22)") (class "Default")
      (node (ref "X1") (pin "22") (pinfunction "GPIO25_22") (pintype "bidirectional"))
    )
    (net (code "48") (name "unconnected-(X1-GPIO26-Pad37)") (class "Default")
      (node (ref "X1") (pin "37") (pinfunction "GPIO26_37") (pintype "no_connect"))
    )
    (net (code "49") (name "unconnected-(X1-GPIO27-Pad13)") (class "Default")
      (node (ref "X1") (pin "13") (pinfunction "GPIO27_13") (pintype "bidirectional"))
    )
    (net (code "50") (name "unconnected-(X1-ID_SC-Pad28)") (class "Default")
      (node (ref "X1") (pin "28") (pinfunction "ID_SC_28") (pintype "no_connect"))
    )
    (net (code "51") (name "unconnected-(X1-ID_SD-Pad27)") (class "Default")
      (node (ref "X1") (pin "27") (pinfunction "ID_SD_27") (pintype "no_connect"))
    )
    (net (code "52") (name "unconnected-(X1-RXD-Pad10)") (class "Default")
      (node (ref "X1") (pin "10") (pinfunction "RXD_10") (pintype "bidirectional"))
    )
    (net (code "53") (name "unconnected-(X1-SCL-Pad5)") (class "Default")
      (node (ref "X1") (pin "5") (pinfunction "SCL_5") (pintype "bidirectional"))
    )
    (net (code "54") (name "unconnected-(X1-SDA-Pad3)") (class "Default")
      (node (ref "X1") (pin "3") (pinfunction "SDA_3") (pintype "bidirectional"))
    )
    (net (code "55") (name "unconnected-(X1-SPI_CE1-Pad26)") (class "Default")
      (node (ref "X1") (pin "26") (pinfunction "SPI_CE1_26") (pintype "bidirectional"))
    )
    (net (code "56") (name "unconnected-(X1-SPI_MISO-Pad21)") (class "Default")
      (node (ref "X1") (pin "21") (pinfunction "SPI_MISO_21") (pintype "bidirectional"))
    )
    (net (code "57") (name "unconnected-(X1-TXD-Pad8)") (class "Default")
      (node (ref "X1") (pin "8") (pinfunction "TXD_8") (pintype "bidirectional"))
    )
  )
)
